# HAL_2.net
KiCad netlist of a schematic drawn in Altium Designer
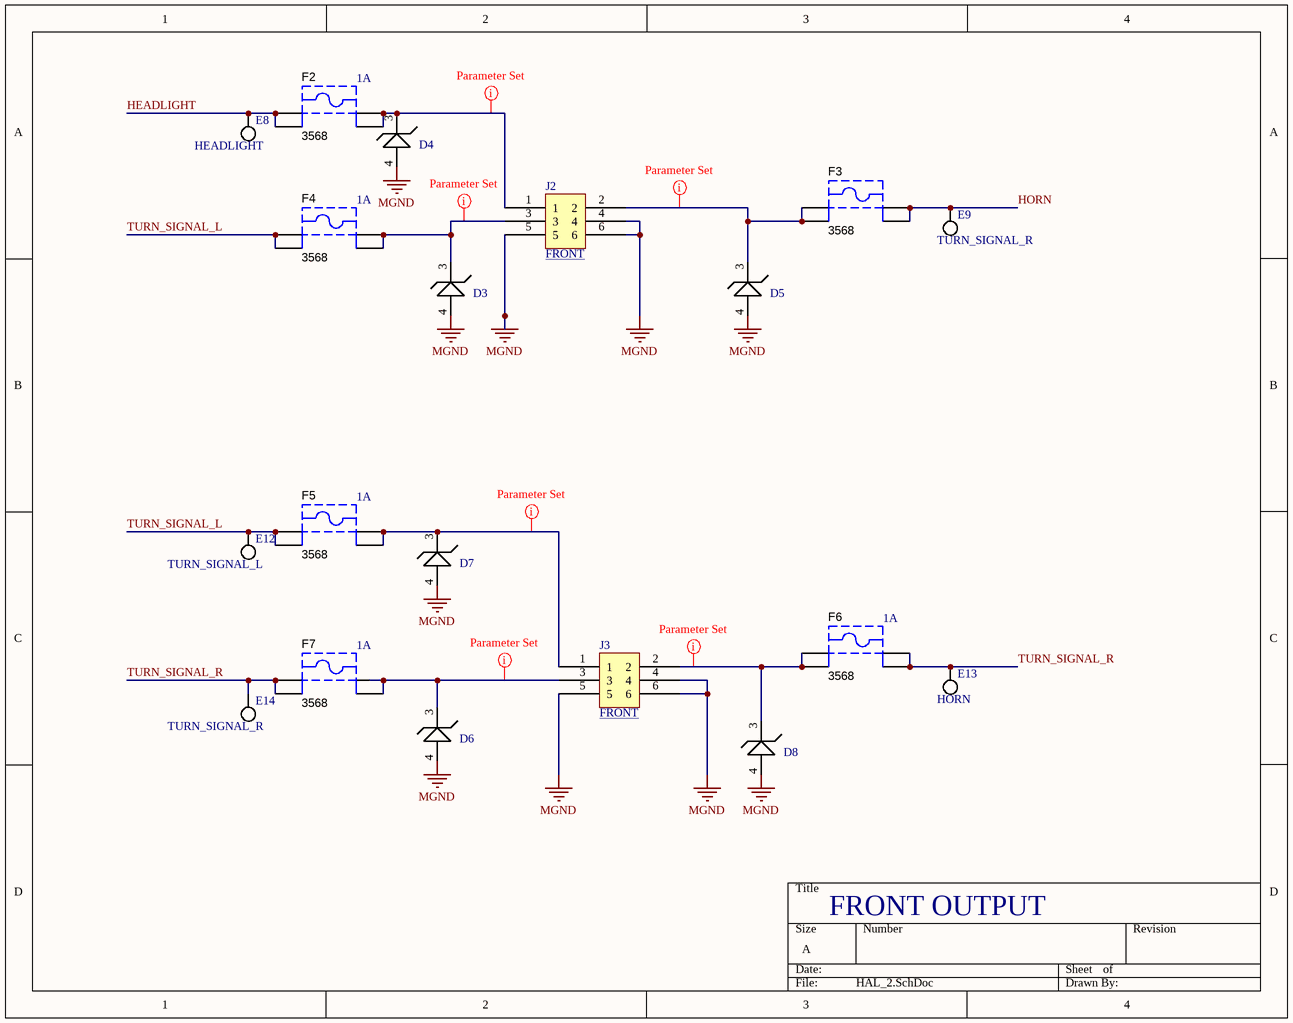
[diagram p0: HAL_2.SchDoc]

(export (version "E")
  (design (tool "Eeschema 10.0.6"))
  (components
    (comp (ref "D3")
      (value "TVS DIODE 12.4V 20.1V DO219AB")
      (footprint "TVS DIODE 12.4V 20.1V DO219AB")
      (libsource (lib "HAL and MotorBoard") (part "TVS DIODE 12.4V 20.1V DO219AB"))
    )
    (comp (ref "D4")
      (value "TVS DIODE 12.4V 20.1V DO219AB")
      (footprint "TVS DIODE 12.4V 20.1V DO219AB")
      (libsource (lib "HAL and MotorBoard") (part "TVS DIODE 12.4V 20.1V DO219AB"))
    )
    (comp (ref "D5")
      (value "TVS DIODE 12.4V 20.1V DO219AB")
      (footprint "TVS DIODE 12.4V 20.1V DO219AB")
      (libsource (lib "HAL and MotorBoard") (part "TVS DIODE 12.4V 20.1V DO219AB"))
    )
    (comp (ref "D6")
      (value "TVS DIODE 12.4V 20.1V DO219AB")
      (footprint "TVS DIODE 12.4V 20.1V DO219AB")
      (libsource (lib "HAL and MotorBoard") (part "TVS DIODE 12.4V 20.1V DO219AB"))
    )
    (comp (ref "D7")
      (value "TVS DIODE 12.4V 20.1V DO219AB")
      (footprint "TVS DIODE 12.4V 20.1V DO219AB")
      (libsource (lib "HAL and MotorBoard") (part "TVS DIODE 12.4V 20.1V DO219AB"))
    )
    (comp (ref "D8")
      (value "TVS DIODE 12.4V 20.1V DO219AB")
      (footprint "TVS DIODE 12.4V 20.1V DO219AB")
      (libsource (lib "HAL and MotorBoard") (part "TVS DIODE 12.4V 20.1V DO219AB"))
    )
    (comp (ref "E8")
      (value "HEADLIGHT")
      (footprint "EPAD")
      (description "Pad for probing signals")
      (libsource (lib "PrISUm-Discrete") (part "EPAD"))
    )
    (comp (ref "E9")
      (value "TURN_SIGNAL_R")
      (footprint "EPAD")
      (description "Pad for probing signals")
      (libsource (lib "PrISUm-Discrete") (part "EPAD"))
    )
    (comp (ref "E12")
      (value "TURN_SIGNAL_L")
      (footprint "EPAD")
      (description "Pad for probing signals")
      (libsource (lib "PrISUm-Discrete") (part "EPAD"))
    )
    (comp (ref "E13")
      (value "HORN")
      (footprint "EPAD")
      (description "Pad for probing signals")
      (libsource (lib "PrISUm-Discrete") (part "EPAD"))
    )
    (comp (ref "E14")
      (value "TURN_SIGNAL_R")
      (footprint "EPAD")
      (description "Pad for probing signals")
      (libsource (lib "PrISUm-Discrete") (part "EPAD"))
    )
    (comp (ref "F2")
      (value "3568")
      (footprint "KSTN-3568_V")
      (description "Fuse Holder, 20 A, 500 V, -50 to 145 degC, 4-Pin THD, RoHS")
      (fields (field (name "MANUFACTURER") "Keystone"))
      (libsource (lib "Altium Content Vault") (part "FUSE_HOLDER-4"))
    )
    (comp (ref "F3")
      (value "3568")
      (footprint "KSTN-3568_V")
      (description "Fuse Holder, 20 A, 500 V, -50 to 145 degC, 4-Pin THD, RoHS")
      (fields (field (name "MANUFACTURER") "Keystone"))
      (libsource (lib "Altium Content Vault") (part "FUSE_HOLDER-4"))
    )
    (comp (ref "F4")
      (value "3568")
      (footprint "KSTN-3568_V")
      (description "Fuse Holder, 20 A, 500 V, -50 to 145 degC, 4-Pin THD, RoHS")
      (fields (field (name "MANUFACTURER") "Keystone"))
      (libsource (lib "Altium Content Vault") (part "FUSE_HOLDER-4"))
    )
    (comp (ref "F5")
      (value "3568")
      (footprint "KSTN-3568_V")
      (description "Fuse Holder, 20 A, 500 V, -50 to 145 degC, 4-Pin THD, RoHS")
      (fields (field (name "MANUFACTURER") "Keystone"))
      (libsource (lib "Altium Content Vault") (part "FUSE_HOLDER-4"))
    )
    (comp (ref "F6")
      (value "3568")
      (footprint "KSTN-3568_V")
      (description "Fuse Holder, 20 A, 500 V, -50 to 145 degC, 4-Pin THD, RoHS")
      (fields (field (name "MANUFACTURER") "Keystone"))
      (libsource (lib "Altium Content Vault") (part "FUSE_HOLDER-4"))
    )
    (comp (ref "F7")
      (value "3568")
      (footprint "KSTN-3568_V")
      (description "Fuse Holder, 20 A, 500 V, -50 to 145 degC, 4-Pin THD, RoHS")
      (fields (field (name "MANUFACTURER") "Keystone"))
      (libsource (lib "Altium Content Vault") (part "FUSE_HOLDER-4"))
    )
    (comp (ref "J2")
      (value "FRONT")
      (footprint "PCBComponent_1 - duplicate")
      (libsource (lib "HAL") (part "6 pin Megafit"))
    )
    (comp (ref "J3")
      (value "FRONT")
      (footprint "PCBComponent_1 - duplicate")
      (libsource (lib "HAL") (part "6 pin Megafit"))
    )
  )
  (nets
    (net (code "1") (name "/HEADLIGHT") (class "Default")
      (node (ref "E8") (pin "1") (pinfunction "1_1") (pintype "passive"))
      (node (ref "F2") (pin "1") (pinfunction "1_1") (pintype "passive"))
      (node (ref "F2") (pin "2") (pinfunction "2_2") (pintype "passive"))
    )
    (net (code "2") (name "/HORN") (class "Default")
      (node (ref "E9") (pin "1") (pinfunction "1_1") (pintype "passive"))
      (node (ref "F3") (pin "3") (pinfunction "3_3") (pintype "passive"))
      (node (ref "F3") (pin "4") (pinfunction "4_4") (pintype "passive"))
    )
    (net (code "3") (name "/TURN_SIGNAL_L") (class "Default")
      (node (ref "E12") (pin "1") (pinfunction "1_1") (pintype "passive"))
      (node (ref "F4") (pin "1") (pinfunction "1_1") (pintype "passive"))
      (node (ref "F4") (pin "2") (pinfunction "2_2") (pintype "passive"))
      (node (ref "F5") (pin "1") (pinfunction "1_1") (pintype "passive"))
      (node (ref "F5") (pin "2") (pinfunction "2_2") (pintype "passive"))
    )
    (net (code "4") (name "/TURN_SIGNAL_R") (class "Default")
      (node (ref "E13") (pin "1") (pinfunction "1_1") (pintype "passive"))
      (node (ref "E14") (pin "1") (pinfunction "1_1") (pintype "passive"))
      (node (ref "F6") (pin "3") (pinfunction "3_3") (pintype "passive"))
      (node (ref "F6") (pin "4") (pinfunction "4_4") (pintype "passive"))
      (node (ref "F7") (pin "1") (pinfunction "1_1") (pintype "passive"))
      (node (ref "F7") (pin "2") (pinfunction "2_2") (pintype "passive"))
    )
    (net (code "5") (name "MGND") (class "Default")
      (node (ref "D3") (pin "4") (pinfunction "4_4") (pintype "passive"))
      (node (ref "D4") (pin "4") (pinfunction "4_4") (pintype "passive"))
      (node (ref "D5") (pin "4") (pinfunction "4_4") (pintype "passive"))
      (node (ref "D6") (pin "4") (pinfunction "4_4") (pintype "passive"))
      (node (ref "D7") (pin "4") (pinfunction "4_4") (pintype "passive"))
      (node (ref "D8") (pin "4") (pinfunction "4_4") (pintype "passive"))
      (node (ref "J2") (pin "4") (pinfunction "4_4") (pintype "passive"))
      (node (ref "J2") (pin "5") (pinfunction "5_5") (pintype "passive"))
      (node (ref "J2") (pin "6") (pinfunction "6_6") (pintype "passive"))
      (node (ref "J3") (pin "4") (pinfunction "4_4") (pintype "passive"))
      (node (ref "J3") (pin "5") (pinfunction "5_5") (pintype "passive"))
      (node (ref "J3") (pin "6") (pinfunction "6_6") (pintype "passive"))
    )
    (net (code "6") (name "Net-(D3-Pad3)") (class "Default")
      (node (ref "D3") (pin "3") (pinfunction "3_3") (pintype "passive"))
      (node (ref "F4") (pin "3") (pinfunction "3_3") (pintype "passive"))
      (node (ref "F4") (pin "4") (pinfunction "4_4") (pintype "passive"))
      (node (ref "J2") (pin "3") (pinfunction "3_3") (pintype "passive"))
    )
    (net (code "7") (name "Net-(D4-Pad3)") (class "Default")
      (node (ref "D4") (pin "3") (pinfunction "3_3") (pintype "passive"))
      (node (ref "F2") (pin "3") (pinfunction "3_3") (pintype "passive"))
      (node (ref "F2") (pin "4") (pinfunction "4_4") (pintype "passive"))
      (node (ref "J2") (pin "1") (pinfunction "1_1") (pintype "passive"))
    )
    (net (code "8") (name "Net-(D5-Pad3)") (class "Default")
      (node (ref "D5") (pin "3") (pinfunction "3_3") (pintype "passive"))
      (node (ref "F3") (pin "1") (pinfunction "1_1") (pintype "passive"))
      (node (ref "F3") (pin "2") (pinfunction "2_2") (pintype "passive"))
      (node (ref "J2") (pin "2") (pinfunction "2_2") (pintype "passive"))
    )
    (net (code "9") (name "Net-(D6-Pad3)") (class "Default")
      (node (ref "D6") (pin "3") (pinfunction "3_3") (pintype "passive"))
      (node (ref "F7") (pin "3") (pinfunction "3_3") (pintype "passive"))
      (node (ref "F7") (pin "4") (pinfunction "4_4") (pintype "passive"))
      (node (ref "J3") (pin "3") (pinfunction "3_3") (pintype "passive"))
    )
    (net (code "10") (name "Net-(D7-Pad3)") (class "Default")
      (node (ref "D7") (pin "3") (pinfunction "3_3") (pintype "passive"))
      (node (ref "F5") (pin "3") (pinfunction "3_3") (pintype "passive"))
      (node (ref "F5") (pin "4") (pinfunction "4_4") (pintype "passive"))
      (node (ref "J3") (pin "1") (pinfunction "1_1") (pintype "passive"))
    )
    (net (code "11") (name "Net-(D8-Pad3)") (class "Default")
      (node (ref "D8") (pin "3") (pinfunction "3_3") (pintype "passive"))
      (node (ref "F6") (pin "1") (pinfunction "1_1") (pintype "passive"))
      (node (ref "F6") (pin "2") (pinfunction "2_2") (pintype "passive"))
      (node (ref "J3") (pin "2") (pinfunction "2_2") (pintype "passive"))
    )
  )
)
